# FPC_Breakout.net
KiCad netlist of a schematic drawn in EAGLE
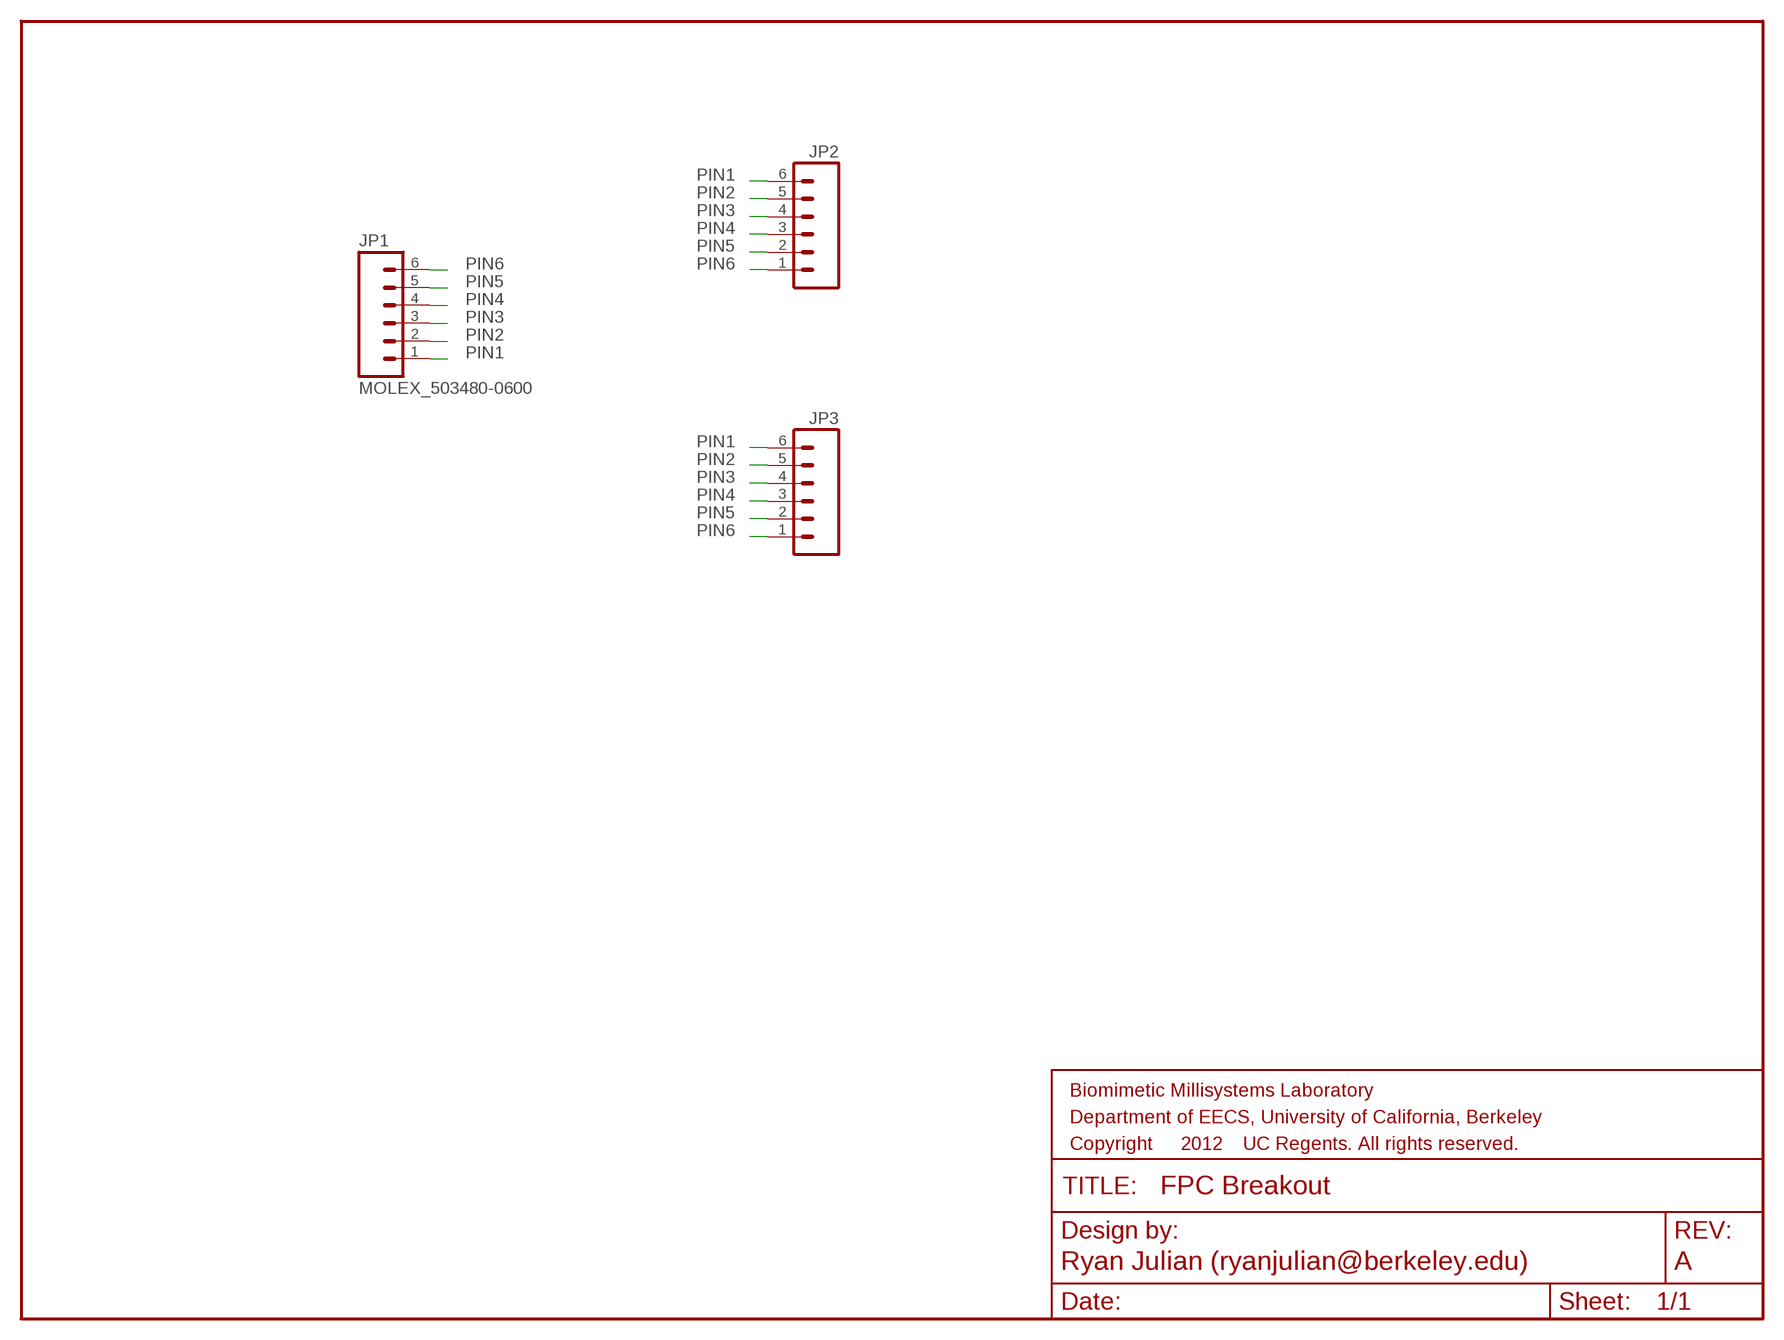
[diagram p0: schematic, sheet 1]

(export (version "E")
  (design (tool "Eeschema 10.0.6"))
  (components
    (comp (ref "JP1")
      (value "MOLEX_503480-0600")
      (footprint "eagle-import:MOLEX_503480-0600")
      (libsource (lib "eagle-import") (part "MOLEX_503480-0600"))
    )
    (comp (ref "JP2")
      (value "M06SIP_LOCK")
      (footprint "eagle-import:1X06-SIP_LOCK")
      (libsource (lib "eagle-import") (part "M06SIP_LOCK"))
    )
    (comp (ref "JP3")
      (value "M061X06-SMD_EDGE_FEMALE")
      (footprint "eagle-import:1X06-SMD_EDGE")
      (libsource (lib "eagle-import") (part "M061X06-SMD_EDGE_FEMALE"))
    )
  )
  (nets
    (net (code "1") (name "/PIN1") (class "Default")
      (node (ref "JP1") (pin "1") (pinfunction "1_1") (pintype "passive"))
      (node (ref "JP2") (pin "6") (pinfunction "6_6") (pintype "passive"))
      (node (ref "JP3") (pin "6") (pinfunction "6_6") (pintype "passive"))
    )
    (net (code "2") (name "/PIN2") (class "Default")
      (node (ref "JP1") (pin "2") (pinfunction "2_2") (pintype "passive"))
      (node (ref "JP2") (pin "5") (pinfunction "5_5") (pintype "passive"))
      (node (ref "JP3") (pin "5") (pinfunction "5_5") (pintype "passive"))
    )
    (net (code "3") (name "/PIN3") (class "Default")
      (node (ref "JP1") (pin "3") (pinfunction "3_3") (pintype "passive"))
      (node (ref "JP2") (pin "4") (pinfunction "4_4") (pintype "passive"))
      (node (ref "JP3") (pin "4") (pinfunction "4_4") (pintype "passive"))
    )
    (net (code "4") (name "/PIN4") (class "Default")
      (node (ref "JP1") (pin "4") (pinfunction "4_4") (pintype "passive"))
      (node (ref "JP2") (pin "3") (pinfunction "3_3") (pintype "passive"))
      (node (ref "JP3") (pin "3") (pinfunction "3_3") (pintype "passive"))
    )
    (net (code "5") (name "/PIN5") (class "Default")
      (node (ref "JP1") (pin "5") (pinfunction "5_5") (pintype "passive"))
      (node (ref "JP2") (pin "2") (pinfunction "2_2") (pintype "passive"))
      (node (ref "JP3") (pin "2") (pinfunction "2_2") (pintype "passive"))
    )
    (net (code "6") (name "/PIN6") (class "Default")
      (node (ref "JP1") (pin "6") (pinfunction "6_6") (pintype "passive"))
      (node (ref "JP2") (pin "1") (pinfunction "1_1") (pintype "passive"))
      (node (ref "JP3") (pin "1") (pinfunction "1_1") (pintype "passive"))
    )
  )
)
